# Dipolefeed.net
KiCad netlist of a schematic drawn in EAGLE
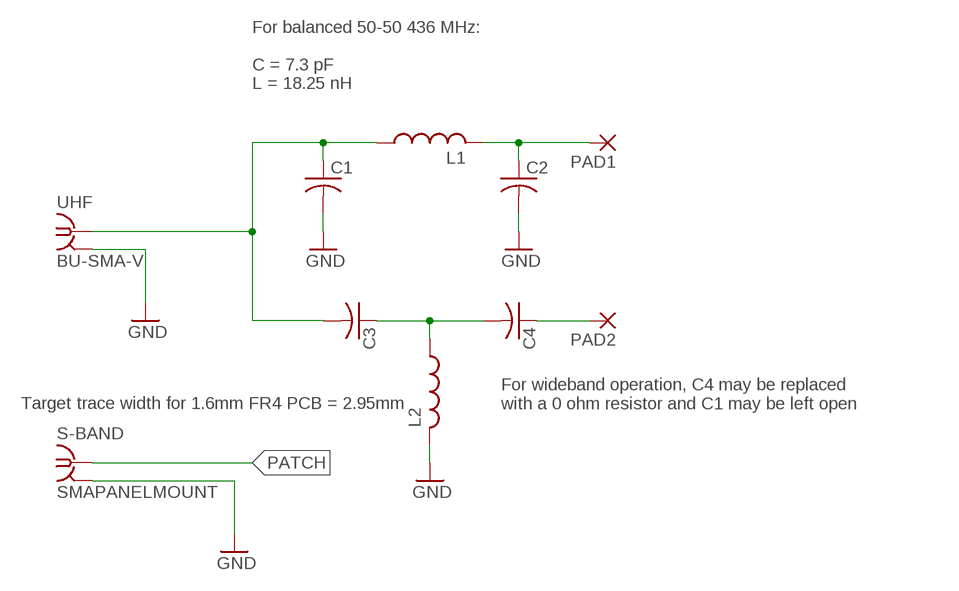
[diagram p0: schematic, sheet 1]

(export (version "E")
  (design (tool "Eeschema 10.0.6"))
  (components
    (comp (ref "C1")
      (value "C-USC1608")
      (footprint "eagle-import:C1608")
      (libsource (lib "eagle-import") (part "C-USC1608"))
    )
    (comp (ref "C2")
      (value "C-USC1608")
      (footprint "eagle-import:C1608")
      (libsource (lib "eagle-import") (part "C-USC1608"))
    )
    (comp (ref "C3")
      (value "C-USC1608")
      (footprint "eagle-import:C1608")
      (libsource (lib "eagle-import") (part "C-USC1608"))
    )
    (comp (ref "C4")
      (value "C-USC1608")
      (footprint "eagle-import:C1608")
      (libsource (lib "eagle-import") (part "C-USC1608"))
    )
    (comp (ref "L1")
      (value "L-USL2012C")
      (footprint "eagle-import:L2012C")
      (libsource (lib "eagle-import") (part "L-USL2012C"))
    )
    (comp (ref "L2")
      (value "L-USL2012C")
      (footprint "eagle-import:L2012C")
      (libsource (lib "eagle-import") (part "L-USL2012C"))
    )
    (comp (ref "PAD1")
      (value "0")
      (footprint "eagle-import:CMMOUNTPAD2")
      (libsource (lib "eagle-import") (part "ANTENNAPAD2"))
    )
    (comp (ref "PAD2")
      (value "180")
      (footprint "eagle-import:CMMOUNTPAD2")
      (libsource (lib "eagle-import") (part "ANTENNAPAD2"))
    )
    (comp (ref "S-BAND")
      (value "SMAPANELMOUNT")
      (footprint "eagle-import:PANELSMA")
      (libsource (lib "eagle-import") (part "SMAPANELMOUNT"))
    )
    (comp (ref "UHF")
      (value "BU-SMA-V")
      (footprint "eagle-import:BU-SMA-V")
      (libsource (lib "eagle-import") (part "BU-SMA-V"))
    )
  )
  (nets
    (net (code "1") (name "GND") (class "Default")
      (node (ref "C1") (pin "2") (pinfunction "2_2") (pintype "passive"))
      (node (ref "C2") (pin "2") (pinfunction "2_2") (pintype "passive"))
      (node (ref "L2") (pin "2") (pinfunction "2_2") (pintype "passive"))
      (node (ref "S-BAND") (pin "P$2") (pinfunction "2_P$2") (pintype "passive"))
      (node (ref "S-BAND") (pin "P$3") (pinfunction "2_P$3") (pintype "passive"))
      (node (ref "UHF") (pin "2") (pinfunction "2_2") (pintype "passive"))
      (node (ref "UHF") (pin "3") (pinfunction "2_3") (pintype "passive"))
      (node (ref "UHF") (pin "4") (pinfunction "2_4") (pintype "passive"))
      (node (ref "UHF") (pin "5") (pinfunction "2_5") (pintype "passive"))
    )
    (net (code "2") (name "Net-(C1-Pad1)") (class "Default")
      (node (ref "C1") (pin "1") (pinfunction "1_1") (pintype "passive"))
      (node (ref "C3") (pin "2") (pinfunction "2_2") (pintype "passive"))
      (node (ref "L1") (pin "1") (pinfunction "1_1") (pintype "passive"))
      (node (ref "UHF") (pin "1") (pinfunction "1_1") (pintype "passive"))
    )
    (net (code "3") (name "Net-(C3-Pad1)") (class "Default")
      (node (ref "C3") (pin "1") (pinfunction "1_1") (pintype "passive"))
      (node (ref "C4") (pin "2") (pinfunction "2_2") (pintype "passive"))
      (node (ref "L2") (pin "1") (pinfunction "1_1") (pintype "passive"))
    )
    (net (code "4") (name "Net-(PAD1-P)") (class "Default")
      (node (ref "C2") (pin "1") (pinfunction "1_1") (pintype "passive"))
      (node (ref "L1") (pin "2") (pinfunction "2_2") (pintype "passive"))
      (node (ref "PAD1") (pin "P$1") (pinfunction "P_P$1") (pintype "passive"))
    )
    (net (code "5") (name "Net-(PAD2-P)") (class "Default")
      (node (ref "C4") (pin "1") (pinfunction "1_1") (pintype "passive"))
      (node (ref "PAD2") (pin "P$1") (pinfunction "P_P$1") (pintype "passive"))
    )
    (net (code "6") (name "PATCH") (class "Default")
      (node (ref "S-BAND") (pin "P$1") (pinfunction "1_P$1") (pintype "passive"))
    )
  )
)
